# SKC_Display.net
KiCad netlist of a schematic drawn in Altium Designer
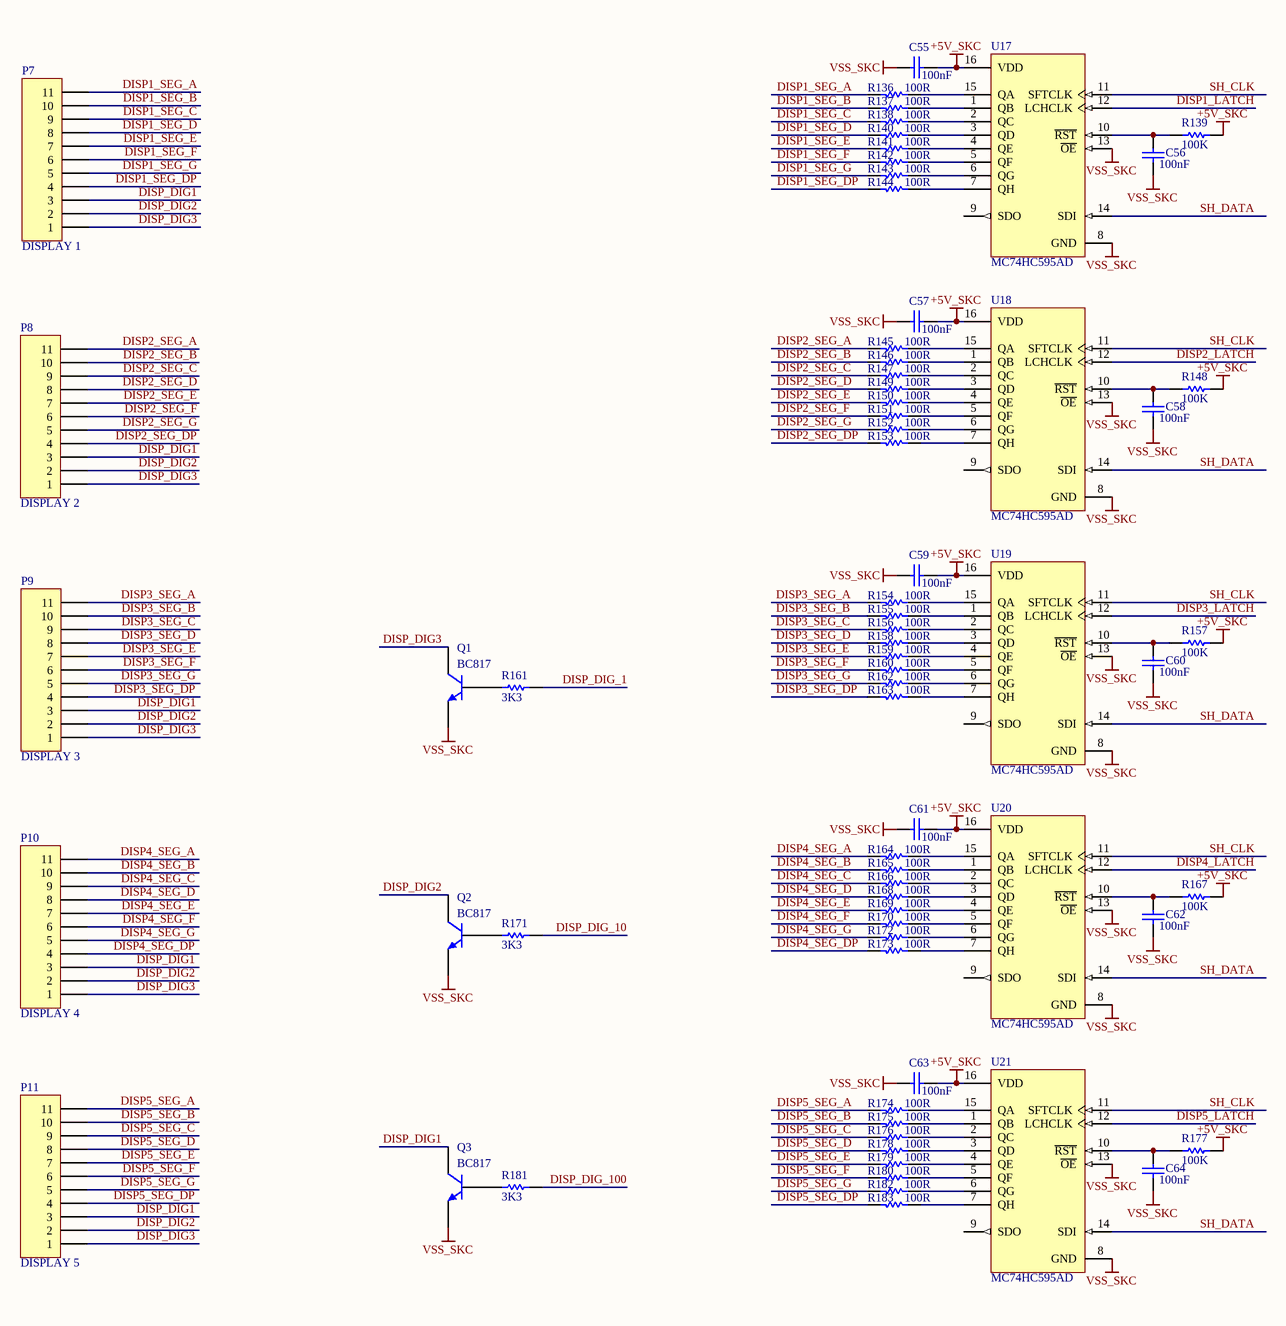
[diagram p0: SKC_Display.SchDoc]

(export (version "E")
  (design (tool "Eeschema 10.0.6"))
  (components
    (comp (ref "C55")
      (value "100nF")
      (footprint "1206")
      (description "Ceramic Chip Capacitor - Standard")
      (fields (field (name "PUBLISHER") "Altium Limited"))
      (libsource (lib "KEMET Chip Capacitor") (part "C1206"))
    )
    (comp (ref "C56")
      (value "100nF")
      (footprint "1206")
      (description "Ceramic Chip Capacitor - Standard")
      (fields (field (name "PUBLISHER") "Altium Limited"))
      (libsource (lib "KEMET Chip Capacitor") (part "C1206"))
    )
    (comp (ref "C57")
      (value "100nF")
      (footprint "1206")
      (description "Ceramic Chip Capacitor - Standard")
      (fields (field (name "PUBLISHER") "Altium Limited"))
      (libsource (lib "KEMET Chip Capacitor") (part "C1206"))
    )
    (comp (ref "C58")
      (value "100nF")
      (footprint "1206")
      (description "Ceramic Chip Capacitor - Standard")
      (fields (field (name "PUBLISHER") "Altium Limited"))
      (libsource (lib "KEMET Chip Capacitor") (part "C1206"))
    )
    (comp (ref "C59")
      (value "100nF")
      (footprint "1206")
      (description "Ceramic Chip Capacitor - Standard")
      (fields (field (name "PUBLISHER") "Altium Limited"))
      (libsource (lib "KEMET Chip Capacitor") (part "C1206"))
    )
    (comp (ref "C60")
      (value "100nF")
      (footprint "1206")
      (description "Ceramic Chip Capacitor - Standard")
      (fields (field (name "PUBLISHER") "Altium Limited"))
      (libsource (lib "KEMET Chip Capacitor") (part "C1206"))
    )
    (comp (ref "C61")
      (value "100nF")
      (footprint "1206")
      (description "Ceramic Chip Capacitor - Standard")
      (fields (field (name "PUBLISHER") "Altium Limited"))
      (libsource (lib "KEMET Chip Capacitor") (part "C1206"))
    )
    (comp (ref "C62")
      (value "100nF")
      (footprint "1206")
      (description "Ceramic Chip Capacitor - Standard")
      (fields (field (name "PUBLISHER") "Altium Limited"))
      (libsource (lib "KEMET Chip Capacitor") (part "C1206"))
    )
    (comp (ref "C63")
      (value "100nF")
      (footprint "1206")
      (description "Ceramic Chip Capacitor - Standard")
      (fields (field (name "PUBLISHER") "Altium Limited"))
      (libsource (lib "KEMET Chip Capacitor") (part "C1206"))
    )
    (comp (ref "C64")
      (value "100nF")
      (footprint "1206")
      (description "Ceramic Chip Capacitor - Standard")
      (fields (field (name "PUBLISHER") "Altium Limited"))
      (libsource (lib "KEMET Chip Capacitor") (part "C1206"))
    )
    (comp (ref "P7")
      (value "DISPLAY 1")
      (footprint "HDR1X11")
      (description "Header, 11-Pin")
      (fields (field (name "PUBLISHER") "Altium Limited"))
      (libsource (lib "Miscellaneous Connectors") (part "Header 11"))
    )
    (comp (ref "P8")
      (value "DISPLAY 2")
      (footprint "HDR1X11")
      (description "Header, 11-Pin")
      (fields (field (name "PUBLISHER") "Altium Limited"))
      (libsource (lib "Miscellaneous Connectors") (part "Header 11"))
    )
    (comp (ref "P9")
      (value "DISPLAY 3")
      (footprint "HDR1X11")
      (description "Header, 11-Pin")
      (fields (field (name "PUBLISHER") "Altium Limited"))
      (libsource (lib "Miscellaneous Connectors") (part "Header 11"))
    )
    (comp (ref "P10")
      (value "DISPLAY 4")
      (footprint "HDR1X11")
      (description "Header, 11-Pin")
      (fields (field (name "PUBLISHER") "Altium Limited"))
      (libsource (lib "Miscellaneous Connectors") (part "Header 11"))
    )
    (comp (ref "P11")
      (value "DISPLAY 5")
      (footprint "HDR1X11")
      (description "Header, 11-Pin")
      (fields (field (name "PUBLISHER") "Altium Limited"))
      (libsource (lib "Miscellaneous Connectors") (part "Header 11"))
    )
    (comp (ref "Q1")
      (value "BC817")
      (footprint "SOT23_N")
      (description "NPN General-purpose Transistor")
      (fields (field (name "PUBLISHER") "Altium Limited"))
      (libsource (lib "Philips Discrete BJT - Low Power") (part "BC817"))
    )
    (comp (ref "Q2")
      (value "BC817")
      (footprint "SOT23_N")
      (description "NPN General-purpose Transistor")
      (fields (field (name "PUBLISHER") "Altium Limited"))
      (libsource (lib "Philips Discrete BJT - Low Power") (part "BC817"))
    )
    (comp (ref "Q3")
      (value "BC817")
      (footprint "SOT23_N")
      (description "NPN General-purpose Transistor")
      (fields (field (name "PUBLISHER") "Altium Limited"))
      (libsource (lib "Philips Discrete BJT - Low Power") (part "BC817"))
    )
    (comp (ref "R136")
      (value "100R")
      (footprint "ERA-0603")
      (fields (field (name "PUBLISHER") "Altium Limited"))
      (libsource (lib "Panasonic Resistor") (part "ERA3Y"))
    )
    (comp (ref "R137")
      (value "100R")
      (footprint "ERA-0603")
      (fields (field (name "PUBLISHER") "Altium Limited"))
      (libsource (lib "Panasonic Resistor") (part "ERA3Y"))
    )
    (comp (ref "R138")
      (value "100R")
      (footprint "ERA-0603")
      (fields (field (name "PUBLISHER") "Altium Limited"))
      (libsource (lib "Panasonic Resistor") (part "ERA3Y"))
    )
    (comp (ref "R139")
      (value "100K")
      (footprint "ERA-0603")
      (fields (field (name "PUBLISHER") "Altium Limited"))
      (libsource (lib "Panasonic Resistor") (part "ERA3Y"))
    )
    (comp (ref "R140")
      (value "100R")
      (footprint "ERA-0603")
      (fields (field (name "PUBLISHER") "Altium Limited"))
      (libsource (lib "Panasonic Resistor") (part "ERA3Y"))
    )
    (comp (ref "R141")
      (value "100R")
      (footprint "ERA-0603")
      (fields (field (name "PUBLISHER") "Altium Limited"))
      (libsource (lib "Panasonic Resistor") (part "ERA3Y"))
    )
    (comp (ref "R142")
      (value "100R")
      (footprint "ERA-0603")
      (fields (field (name "PUBLISHER") "Altium Limited"))
      (libsource (lib "Panasonic Resistor") (part "ERA3Y"))
    )
    (comp (ref "R143")
      (value "100R")
      (footprint "ERA-0603")
      (fields (field (name "PUBLISHER") "Altium Limited"))
      (libsource (lib "Panasonic Resistor") (part "ERA3Y"))
    )
    (comp (ref "R144")
      (value "100R")
      (footprint "ERA-0603")
      (fields (field (name "PUBLISHER") "Altium Limited"))
      (libsource (lib "Panasonic Resistor") (part "ERA3Y"))
    )
    (comp (ref "R145")
      (value "100R")
      (footprint "ERA-0603")
      (fields (field (name "PUBLISHER") "Altium Limited"))
      (libsource (lib "Panasonic Resistor") (part "ERA3Y"))
    )
    (comp (ref "R146")
      (value "100R")
      (footprint "ERA-0603")
      (fields (field (name "PUBLISHER") "Altium Limited"))
      (libsource (lib "Panasonic Resistor") (part "ERA3Y"))
    )
    (comp (ref "R147")
      (value "100R")
      (footprint "ERA-0603")
      (fields (field (name "PUBLISHER") "Altium Limited"))
      (libsource (lib "Panasonic Resistor") (part "ERA3Y"))
    )
    (comp (ref "R148")
      (value "100K")
      (footprint "ERA-0603")
      (fields (field (name "PUBLISHER") "Altium Limited"))
      (libsource (lib "Panasonic Resistor") (part "ERA3Y"))
    )
    (comp (ref "R149")
      (value "100R")
      (footprint "ERA-0603")
      (fields (field (name "PUBLISHER") "Altium Limited"))
      (libsource (lib "Panasonic Resistor") (part "ERA3Y"))
    )
    (comp (ref "R150")
      (value "100R")
      (footprint "ERA-0603")
      (fields (field (name "PUBLISHER") "Altium Limited"))
      (libsource (lib "Panasonic Resistor") (part "ERA3Y"))
    )
    (comp (ref "R151")
      (value "100R")
      (footprint "ERA-0603")
      (fields (field (name "PUBLISHER") "Altium Limited"))
      (libsource (lib "Panasonic Resistor") (part "ERA3Y"))
    )
    (comp (ref "R152")
      (value "100R")
      (footprint "ERA-0603")
      (fields (field (name "PUBLISHER") "Altium Limited"))
      (libsource (lib "Panasonic Resistor") (part "ERA3Y"))
    )
    (comp (ref "R153")
      (value "100R")
      (footprint "ERA-0603")
      (fields (field (name "PUBLISHER") "Altium Limited"))
      (libsource (lib "Panasonic Resistor") (part "ERA3Y"))
    )
    (comp (ref "R154")
      (value "100R")
      (footprint "ERA-0603")
      (fields (field (name "PUBLISHER") "Altium Limited"))
      (libsource (lib "Panasonic Resistor") (part "ERA3Y"))
    )
    (comp (ref "R155")
      (value "100R")
      (footprint "ERA-0603")
      (fields (field (name "PUBLISHER") "Altium Limited"))
      (libsource (lib "Panasonic Resistor") (part "ERA3Y"))
    )
    (comp (ref "R156")
      (value "100R")
      (footprint "ERA-0603")
      (fields (field (name "PUBLISHER") "Altium Limited"))
      (libsource (lib "Panasonic Resistor") (part "ERA3Y"))
    )
    (comp (ref "R157")
      (value "100K")
      (footprint "ERA-0603")
      (fields (field (name "PUBLISHER") "Altium Limited"))
      (libsource (lib "Panasonic Resistor") (part "ERA3Y"))
    )
    (comp (ref "R158")
      (value "100R")
      (footprint "ERA-0603")
      (fields (field (name "PUBLISHER") "Altium Limited"))
      (libsource (lib "Panasonic Resistor") (part "ERA3Y"))
    )
    (comp (ref "R159")
      (value "100R")
      (footprint "ERA-0603")
      (fields (field (name "PUBLISHER") "Altium Limited"))
      (libsource (lib "Panasonic Resistor") (part "ERA3Y"))
    )
    (comp (ref "R160")
      (value "100R")
      (footprint "ERA-0603")
      (fields (field (name "PUBLISHER") "Altium Limited"))
      (libsource (lib "Panasonic Resistor") (part "ERA3Y"))
    )
    (comp (ref "R161")
      (value "3K3")
      (footprint "ERA-0603")
      (fields (field (name "PUBLISHER") "Altium Limited"))
      (libsource (lib "Panasonic Resistor") (part "ERA3Y"))
    )
    (comp (ref "R162")
      (value "100R")
      (footprint "ERA-0603")
      (fields (field (name "PUBLISHER") "Altium Limited"))
      (libsource (lib "Panasonic Resistor") (part "ERA3Y"))
    )
    (comp (ref "R163")
      (value "100R")
      (footprint "ERA-0603")
      (fields (field (name "PUBLISHER") "Altium Limited"))
      (libsource (lib "Panasonic Resistor") (part "ERA3Y"))
    )
    (comp (ref "R164")
      (value "100R")
      (footprint "ERA-0603")
      (fields (field (name "PUBLISHER") "Altium Limited"))
      (libsource (lib "Panasonic Resistor") (part "ERA3Y"))
    )
    (comp (ref "R165")
      (value "100R")
      (footprint "ERA-0603")
      (fields (field (name "PUBLISHER") "Altium Limited"))
      (libsource (lib "Panasonic Resistor") (part "ERA3Y"))
    )
    (comp (ref "R166")
      (value "100R")
      (footprint "ERA-0603")
      (fields (field (name "PUBLISHER") "Altium Limited"))
      (libsource (lib "Panasonic Resistor") (part "ERA3Y"))
    )
    (comp (ref "R167")
      (value "100K")
      (footprint "ERA-0603")
      (fields (field (name "PUBLISHER") "Altium Limited"))
      (libsource (lib "Panasonic Resistor") (part "ERA3Y"))
    )
    (comp (ref "R168")
      (value "100R")
      (footprint "ERA-0603")
      (fields (field (name "PUBLISHER") "Altium Limited"))
      (libsource (lib "Panasonic Resistor") (part "ERA3Y"))
    )
    (comp (ref "R169")
      (value "100R")
      (footprint "ERA-0603")
      (fields (field (name "PUBLISHER") "Altium Limited"))
      (libsource (lib "Panasonic Resistor") (part "ERA3Y"))
    )
    (comp (ref "R170")
      (value "100R")
      (footprint "ERA-0603")
      (fields (field (name "PUBLISHER") "Altium Limited"))
      (libsource (lib "Panasonic Resistor") (part "ERA3Y"))
    )
    (comp (ref "R171")
      (value "3K3")
      (footprint "ERA-0603")
      (fields (field (name "PUBLISHER") "Altium Limited"))
      (libsource (lib "Panasonic Resistor") (part "ERA3Y"))
    )
    (comp (ref "R172")
      (value "100R")
      (footprint "ERA-0603")
      (fields (field (name "PUBLISHER") "Altium Limited"))
      (libsource (lib "Panasonic Resistor") (part "ERA3Y"))
    )
    (comp (ref "R173")
      (value "100R")
      (footprint "ERA-0603")
      (fields (field (name "PUBLISHER") "Altium Limited"))
      (libsource (lib "Panasonic Resistor") (part "ERA3Y"))
    )
    (comp (ref "R174")
      (value "100R")
      (footprint "ERA-0603")
      (fields (field (name "PUBLISHER") "Altium Limited"))
      (libsource (lib "Panasonic Resistor") (part "ERA3Y"))
    )
    (comp (ref "R175")
      (value "100R")
      (footprint "ERA-0603")
      (fields (field (name "PUBLISHER") "Altium Limited"))
      (libsource (lib "Panasonic Resistor") (part "ERA3Y"))
    )
    (comp (ref "R176")
      (value "100R")
      (footprint "ERA-0603")
      (fields (field (name "PUBLISHER") "Altium Limited"))
      (libsource (lib "Panasonic Resistor") (part "ERA3Y"))
    )
    (comp (ref "R177")
      (value "100K")
      (footprint "ERA-0603")
      (fields (field (name "PUBLISHER") "Altium Limited"))
      (libsource (lib "Panasonic Resistor") (part "ERA3Y"))
    )
    (comp (ref "R178")
      (value "100R")
      (footprint "ERA-0603")
      (fields (field (name "PUBLISHER") "Altium Limited"))
      (libsource (lib "Panasonic Resistor") (part "ERA3Y"))
    )
    (comp (ref "R179")
      (value "100R")
      (footprint "ERA-0603")
      (fields (field (name "PUBLISHER") "Altium Limited"))
      (libsource (lib "Panasonic Resistor") (part "ERA3Y"))
    )
    (comp (ref "R180")
      (value "100R")
      (footprint "ERA-0603")
      (fields (field (name "PUBLISHER") "Altium Limited"))
      (libsource (lib "Panasonic Resistor") (part "ERA3Y"))
    )
    (comp (ref "R181")
      (value "3K3")
      (footprint "ERA-0603")
      (fields (field (name "PUBLISHER") "Altium Limited"))
      (libsource (lib "Panasonic Resistor") (part "ERA3Y"))
    )
    (comp (ref "R182")
      (value "100R")
      (footprint "ERA-0603")
      (fields (field (name "PUBLISHER") "Altium Limited"))
      (libsource (lib "Panasonic Resistor") (part "ERA3Y"))
    )
    (comp (ref "R183")
      (value "100R")
      (footprint "ERA-0603")
      (fields (field (name "PUBLISHER") "Altium Limited"))
      (libsource (lib "Panasonic Resistor") (part "ERA3Y"))
    )
    (comp (ref "U17")
      (value "MC74HC595AD")
      (footprint "751B-05_N")
      (description "8-Bit Serial-Input/Serial or Prallel-Output Shift Register with Latched 3-State Outputs")
      (fields (field (name "PUBLISHER") "Altium Limited"))
      (libsource (lib "ON Semi Logic Register") (part "MC74HC595AD"))
    )
    (comp (ref "U18")
      (value "MC74HC595AD")
      (footprint "751B-05_N")
      (description "8-Bit Serial-Input/Serial or Prallel-Output Shift Register with Latched 3-State Outputs")
      (fields (field (name "PUBLISHER") "Altium Limited"))
      (libsource (lib "ON Semi Logic Register") (part "MC74HC595AD"))
    )
    (comp (ref "U19")
      (value "MC74HC595AD")
      (footprint "751B-05_N")
      (description "8-Bit Serial-Input/Serial or Prallel-Output Shift Register with Latched 3-State Outputs")
      (fields (field (name "PUBLISHER") "Altium Limited"))
      (libsource (lib "ON Semi Logic Register") (part "MC74HC595AD"))
    )
    (comp (ref "U20")
      (value "MC74HC595AD")
      (footprint "751B-05_N")
      (description "8-Bit Serial-Input/Serial or Prallel-Output Shift Register with Latched 3-State Outputs")
      (fields (field (name "PUBLISHER") "Altium Limited"))
      (libsource (lib "ON Semi Logic Register") (part "MC74HC595AD"))
    )
    (comp (ref "U21")
      (value "MC74HC595AD")
      (footprint "751B-05_N")
      (description "8-Bit Serial-Input/Serial or Prallel-Output Shift Register with Latched 3-State Outputs")
      (fields (field (name "PUBLISHER") "Altium Limited"))
      (libsource (lib "ON Semi Logic Register") (part "MC74HC595AD"))
    )
  )
  (nets
    (net (code "1") (name "+5V_SKC") (class "Default")
      (node (ref "C55") (pin "1") (pinfunction "1_1") (pintype "passive"))
      (node (ref "C57") (pin "1") (pinfunction "1_1") (pintype "passive"))
      (node (ref "C59") (pin "1") (pinfunction "1_1") (pintype "passive"))
      (node (ref "C61") (pin "1") (pinfunction "1_1") (pintype "passive"))
      (node (ref "C63") (pin "1") (pinfunction "1_1") (pintype "passive"))
      (node (ref "R139") (pin "2") (pinfunction "2_2") (pintype "passive"))
      (node (ref "R148") (pin "2") (pinfunction "2_2") (pintype "passive"))
      (node (ref "R157") (pin "2") (pinfunction "2_2") (pintype "passive"))
      (node (ref "R167") (pin "2") (pinfunction "2_2") (pintype "passive"))
      (node (ref "R177") (pin "2") (pinfunction "2_2") (pintype "passive"))
      (node (ref "U17") (pin "16") (pinfunction "VDD_16") (pintype "power_in"))
      (node (ref "U18") (pin "16") (pinfunction "VDD_16") (pintype "power_in"))
      (node (ref "U19") (pin "16") (pinfunction "VDD_16") (pintype "power_in"))
      (node (ref "U20") (pin "16") (pinfunction "VDD_16") (pintype "power_in"))
      (node (ref "U21") (pin "16") (pinfunction "VDD_16") (pintype "power_in"))
    )
    (net (code "2") (name "/DISP1_LATCH") (class "Default")
      (node (ref "U17") (pin "12") (pinfunction "LCHCLK_12") (pintype "input"))
    )
    (net (code "3") (name "/DISP1_SEG_A") (class "Default")
      (node (ref "P7") (pin "11") (pinfunction "11_11") (pintype "passive"))
      (node (ref "R136") (pin "2") (pinfunction "2_2") (pintype "passive"))
    )
    (net (code "4") (name "/DISP1_SEG_B") (class "Default")
      (node (ref "P7") (pin "10") (pinfunction "10_10") (pintype "passive"))
      (node (ref "R137") (pin "2") (pinfunction "2_2") (pintype "passive"))
    )
    (net (code "5") (name "/DISP1_SEG_C") (class "Default")
      (node (ref "P7") (pin "9") (pinfunction "9_9") (pintype "passive"))
      (node (ref "R138") (pin "2") (pinfunction "2_2") (pintype "passive"))
    )
    (net (code "6") (name "/DISP1_SEG_D") (class "Default")
      (node (ref "P7") (pin "8") (pinfunction "8_8") (pintype "passive"))
      (node (ref "R140") (pin "2") (pinfunction "2_2") (pintype "passive"))
    )
    (net (code "7") (name "/DISP1_SEG_DP") (class "Default")
      (node (ref "P7") (pin "4") (pinfunction "4_4") (pintype "passive"))
      (node (ref "R144") (pin "2") (pinfunction "2_2") (pintype "passive"))
    )
    (net (code "8") (name "/DISP1_SEG_E") (class "Default")
      (node (ref "P7") (pin "7") (pinfunction "7_7") (pintype "passive"))
      (node (ref "R141") (pin "2") (pinfunction "2_2") (pintype "passive"))
    )
    (net (code "9") (name "/DISP1_SEG_F") (class "Default")
      (node (ref "P7") (pin "6") (pinfunction "6_6") (pintype "passive"))
      (node (ref "R142") (pin "2") (pinfunction "2_2") (pintype "passive"))
    )
    (net (code "10") (name "/DISP1_SEG_G") (class "Default")
      (node (ref "P7") (pin "5") (pinfunction "5_5") (pintype "passive"))
      (node (ref "R143") (pin "2") (pinfunction "2_2") (pintype "passive"))
    )
    (net (code "11") (name "/DISP2_LATCH") (class "Default")
      (node (ref "U18") (pin "12") (pinfunction "LCHCLK_12") (pintype "input"))
    )
    (net (code "12") (name "/DISP2_SEG_A") (class "Default")
      (node (ref "P8") (pin "11") (pinfunction "11_11") (pintype "passive"))
      (node (ref "R145") (pin "2") (pinfunction "2_2") (pintype "passive"))
    )
    (net (code "13") (name "/DISP2_SEG_B") (class "Default")
      (node (ref "P8") (pin "10") (pinfunction "10_10") (pintype "passive"))
      (node (ref "R146") (pin "2") (pinfunction "2_2") (pintype "passive"))
    )
    (net (code "14") (name "/DISP2_SEG_C") (class "Default")
      (node (ref "P8") (pin "9") (pinfunction "9_9") (pintype "passive"))
      (node (ref "R147") (pin "2") (pinfunction "2_2") (pintype "passive"))
    )
    (net (code "15") (name "/DISP2_SEG_D") (class "Default")
      (node (ref "P8") (pin "8") (pinfunction "8_8") (pintype "passive"))
      (node (ref "R149") (pin "2") (pinfunction "2_2") (pintype "passive"))
    )
    (net (code "16") (name "/DISP2_SEG_DP") (class "Default")
      (node (ref "P8") (pin "4") (pinfunction "4_4") (pintype "passive"))
      (node (ref "R153") (pin "2") (pinfunction "2_2") (pintype "passive"))
    )
    (net (code "17") (name "/DISP2_SEG_E") (class "Default")
      (node (ref "P8") (pin "7") (pinfunction "7_7") (pintype "passive"))
      (node (ref "R150") (pin "2") (pinfunction "2_2") (pintype "passive"))
    )
    (net (code "18") (name "/DISP2_SEG_F") (class "Default")
      (node (ref "P8") (pin "6") (pinfunction "6_6") (pintype "passive"))
      (node (ref "R151") (pin "2") (pinfunction "2_2") (pintype "passive"))
    )
    (net (code "19") (name "/DISP2_SEG_G") (class "Default")
      (node (ref "P8") (pin "5") (pinfunction "5_5") (pintype "passive"))
      (node (ref "R152") (pin "2") (pinfunction "2_2") (pintype "passive"))
    )
    (net (code "20") (name "/DISP3_LATCH") (class "Default")
      (node (ref "U19") (pin "12") (pinfunction "LCHCLK_12") (pintype "input"))
    )
    (net (code "21") (name "/DISP3_SEG_A") (class "Default")
      (node (ref "P9") (pin "11") (pinfunction "11_11") (pintype "passive"))
      (node (ref "R154") (pin "2") (pinfunction "2_2") (pintype "passive"))
    )
    (net (code "22") (name "/DISP3_SEG_B") (class "Default")
      (node (ref "P9") (pin "10") (pinfunction "10_10") (pintype "passive"))
      (node (ref "R155") (pin "2") (pinfunction "2_2") (pintype "passive"))
    )
    (net (code "23") (name "/DISP3_SEG_C") (class "Default")
      (node (ref "P9") (pin "9") (pinfunction "9_9") (pintype "passive"))
      (node (ref "R156") (pin "2") (pinfunction "2_2") (pintype "passive"))
    )
    (net (code "24") (name "/DISP3_SEG_D") (class "Default")
      (node (ref "P9") (pin "8") (pinfunction "8_8") (pintype "passive"))
      (node (ref "R158") (pin "2") (pinfunction "2_2") (pintype "passive"))
    )
    (net (code "25") (name "/DISP3_SEG_DP") (class "Default")
      (node (ref "P9") (pin "4") (pinfunction "4_4") (pintype "passive"))
      (node (ref "R163") (pin "2") (pinfunction "2_2") (pintype "passive"))
    )
    (net (code "26") (name "/DISP3_SEG_E") (class "Default")
      (node (ref "P9") (pin "7") (pinfunction "7_7") (pintype "passive"))
      (node (ref "R159") (pin "2") (pinfunction "2_2") (pintype "passive"))
    )
    (net (code "27") (name "/DISP3_SEG_F") (class "Default")
      (node (ref "P9") (pin "6") (pinfunction "6_6") (pintype "passive"))
      (node (ref "R160") (pin "2") (pinfunction "2_2") (pintype "passive"))
    )
    (net (code "28") (name "/DISP3_SEG_G") (class "Default")
      (node (ref "P9") (pin "5") (pinfunction "5_5") (pintype "passive"))
      (node (ref "R162") (pin "2") (pinfunction "2_2") (pintype "passive"))
    )
    (net (code "29") (name "/DISP4_LATCH") (class "Default")
      (node (ref "U20") (pin "12") (pinfunction "LCHCLK_12") (pintype "input"))
    )
    (net (code "30") (name "/DISP4_SEG_A") (class "Default")
      (node (ref "P10") (pin "11") (pinfunction "11_11") (pintype "passive"))
      (node (ref "R164") (pin "2") (pinfunction "2_2") (pintype "passive"))
    )
    (net (code "31") (name "/DISP4_SEG_B") (class "Default")
      (node (ref "P10") (pin "10") (pinfunction "10_10") (pintype "passive"))
      (node (ref "R165") (pin "2") (pinfunction "2_2") (pintype "passive"))
    )
    (net (code "32") (name "/DISP4_SEG_C") (class "Default")
      (node (ref "P10") (pin "9") (pinfunction "9_9") (pintype "passive"))
      (node (ref "R166") (pin "2") (pinfunction "2_2") (pintype "passive"))
    )
    (net (code "33") (name "/DISP4_SEG_D") (class "Default")
      (node (ref "P10") (pin "8") (pinfunction "8_8") (pintype "passive"))
      (node (ref "R168") (pin "2") (pinfunction "2_2") (pintype "passive"))
    )
    (net (code "34") (name "/DISP4_SEG_DP") (class "Default")
      (node (ref "P10") (pin "4") (pinfunction "4_4") (pintype "passive"))
      (node (ref "R173") (pin "2") (pinfunction "2_2") (pintype "passive"))
    )
    (net (code "35") (name "/DISP4_SEG_E") (class "Default")
      (node (ref "P10") (pin "7") (pinfunction "7_7") (pintype "passive"))
      (node (ref "R169") (pin "2") (pinfunction "2_2") (pintype "passive"))
    )
    (net (code "36") (name "/DISP4_SEG_F") (class "Default")
      (node (ref "P10") (pin "6") (pinfunction "6_6") (pintype "passive"))
      (node (ref "R170") (pin "2") (pinfunction "2_2") (pintype "passive"))
    )
    (net (code "37") (name "/DISP4_SEG_G") (class "Default")
      (node (ref "P10") (pin "5") (pinfunction "5_5") (pintype "passive"))
      (node (ref "R172") (pin "2") (pinfunction "2_2") (pintype "passive"))
    )
    (net (code "38") (name "/DISP5_LATCH") (class "Default")
      (node (ref "U21") (pin "12") (pinfunction "LCHCLK_12") (pintype "input"))
    )
    (net (code "39") (name "/DISP5_SEG_A") (class "Default")
      (node (ref "P11") (pin "11") (pinfunction "11_11") (pintype "passive"))
      (node (ref "R174") (pin "2") (pinfunction "2_2") (pintype "passive"))
    )
    (net (code "40") (name "/DISP5_SEG_B") (class "Default")
      (node (ref "P11") (pin "10") (pinfunction "10_10") (pintype "passive"))
      (node (ref "R175") (pin "2") (pinfunction "2_2") (pintype "passive"))
    )
    (net (code "41") (name "/DISP5_SEG_C") (class "Default")
      (node (ref "P11") (pin "9") (pinfunction "9_9") (pintype "passive"))
      (node (ref "R176") (pin "2") (pinfunction "2_2") (pintype "passive"))
    )
    (net (code "42") (name "/DISP5_SEG_D") (class "Default")
      (node (ref "P11") (pin "8") (pinfunction "8_8") (pintype "passive"))
      (node (ref "R178") (pin "2") (pinfunction "2_2") (pintype "passive"))
    )
    (net (code "43") (name "/DISP5_SEG_DP") (class "Default")
      (node (ref "P11") (pin "4") (pinfunction "4_4") (pintype "passive"))
      (node (ref "R183") (pin "2") (pinfunction "2_2") (pintype "passive"))
    )
    (net (code "44") (name "/DISP5_SEG_E") (class "Default")
      (node (ref "P11") (pin "7") (pinfunction "7_7") (pintype "passive"))
      (node (ref "R179") (pin "2") (pinfunction "2_2") (pintype "passive"))
    )
    (net (code "45") (name "/DISP5_SEG_F") (class "Default")
      (node (ref "P11") (pin "6") (pinfunction "6_6") (pintype "passive"))
      (node (ref "R180") (pin "2") (pinfunction "2_2") (pintype "passive"))
    )
    (net (code "46") (name "/DISP5_SEG_G") (class "Default")
      (node (ref "P11") (pin "5") (pinfunction "5_5") (pintype "passive"))
      (node (ref "R182") (pin "2") (pinfunction "2_2") (pintype "passive"))
    )
    (net (code "47") (name "/DISP_DIG1") (class "Default")
      (node (ref "P10") (pin "3") (pinfunction "3_3") (pintype "passive"))
      (node (ref "P11") (pin "3") (pinfunction "3_3") (pintype "passive"))
      (node (ref "P7") (pin "3") (pinfunction "3_3") (pintype "passive"))
      (node (ref "P8") (pin "3") (pinfunction "3_3") (pintype "passive"))
      (node (ref "P9") (pin "3") (pinfunction "3_3") (pintype "passive"))
      (node (ref "Q3") (pin "3") (pinfunction "C_3") (pintype "passive"))
    )
    (net (code "48") (name "/DISP_DIG2") (class "Default")
      (node (ref "P10") (pin "2") (pinfunction "2_2") (pintype "passive"))
      (node (ref "P11") (pin "2") (pinfunction "2_2") (pintype "passive"))
      (node (ref "P7") (pin "2") (pinfunction "2_2") (pintype "passive"))
      (node (ref "P8") (pin "2") (pinfunction "2_2") (pintype "passive"))
      (node (ref "P9") (pin "2") (pinfunction "2_2") (pintype "passive"))
      (node (ref "Q2") (pin "3") (pinfunction "C_3") (pintype "passive"))
    )
    (net (code "49") (name "/DISP_DIG3") (class "Default")
      (node (ref "P10") (pin "1") (pinfunction "1_1") (pintype "passive"))
      (node (ref "P11") (pin "1") (pinfunction "1_1") (pintype "passive"))
      (node (ref "P7") (pin "1") (pinfunction "1_1") (pintype "passive"))
      (node (ref "P8") (pin "1") (pinfunction "1_1") (pintype "passive"))
      (node (ref "P9") (pin "1") (pinfunction "1_1") (pintype "passive"))
      (node (ref "Q1") (pin "3") (pinfunction "C_3") (pintype "passive"))
    )
    (net (code "50") (name "/DISP_DIG_1") (class "Default")
      (node (ref "R161") (pin "2") (pinfunction "2_2") (pintype "passive"))
    )
    (net (code "51") (name "/DISP_DIG_10") (class "Default")
      (node (ref "R171") (pin "2") (pinfunction "2_2") (pintype "passive"))
    )
    (net (code "52") (name "/DISP_DIG_100") (class "Default")
      (node (ref "R181") (pin "2") (pinfunction "2_2") (pintype "passive"))
    )
    (net (code "53") (name "/SH_CLK") (class "Default")
      (node (ref "U17") (pin "11") (pinfunction "SFTCLK_11") (pintype "input"))
      (node (ref "U18") (pin "11") (pinfunction "SFTCLK_11") (pintype "input"))
      (node (ref "U19") (pin "11") (pinfunction "SFTCLK_11") (pintype "input"))
      (node (ref "U20") (pin "11") (pinfunction "SFTCLK_11") (pintype "input"))
      (node (ref "U21") (pin "11") (pinfunction "SFTCLK_11") (pintype "input"))
    )
    (net (code "54") (name "/SH_DATA") (class "Default")
      (node (ref "U17") (pin "14") (pinfunction "SDI_14") (pintype "input"))
      (node (ref "U18") (pin "14") (pinfunction "SDI_14") (pintype "input"))
      (node (ref "U19") (pin "14") (pinfunction "SDI_14") (pintype "input"))
      (node (ref "U20") (pin "14") (pinfunction "SDI_14") (pintype "input"))
      (node (ref "U21") (pin "14") (pinfunction "SDI_14") (pintype "input"))
    )
    (net (code "55") (name "Net-(Q1-B)") (class "Default")
      (node (ref "Q1") (pin "1") (pinfunction "B_1") (pintype "passive"))
      (node (ref "R161") (pin "1") (pinfunction "1_1") (pintype "passive"))
    )
    (net (code "56") (name "Net-(Q2-B)") (class "Default")
      (node (ref "Q2") (pin "1") (pinfunction "B_1") (pintype "passive"))
      (node (ref "R171") (pin "1") (pinfunction "1_1") (pintype "passive"))
    )
    (net (code "57") (name "Net-(Q3-B)") (class "Default")
      (node (ref "Q3") (pin "1") (pinfunction "B_1") (pintype "passive"))
      (node (ref "R181") (pin "1") (pinfunction "1_1") (pintype "passive"))
    )
    (net (code "58") (name "Net-(U17-QA)") (class "Default")
      (node (ref "R136") (pin "1") (pinfunction "1_1") (pintype "passive"))
      (node (ref "U17") (pin "15") (pinfunction "QA_15") (pintype "tri_state"))
    )
    (net (code "59") (name "Net-(U17-QB)") (class "Default")
      (node (ref "R137") (pin "1") (pinfunction "1_1") (pintype "passive"))
      (node (ref "U17") (pin "1") (pinfunction "QB_1") (pintype "tri_state"))
    )
    (net (code "60") (name "Net-(U17-QC)") (class "Default")
      (node (ref "R138") (pin "1") (pinfunction "1_1") (pintype "passive"))
      (node (ref "U17") (pin "2") (pinfunction "QC_2") (pintype "tri_state"))
    )
    (net (code "61") (name "Net-(U17-QD)") (class "Default")
      (node (ref "R140") (pin "1") (pinfunction "1_1") (pintype "passive"))
      (node (ref "U17") (pin "3") (pinfunction "QD_3") (pintype "tri_state"))
    )
    (net (code "62") (name "Net-(U17-QE)") (class "Default")
      (node (ref "R141") (pin "1") (pinfunction "1_1") (pintype "passive"))
      (node (ref "U17") (pin "4") (pinfunction "QE_4") (pintype "tri_state"))
    )
    (net (code "63") (name "Net-(U17-QF)") (class "Default")
      (node (ref "R142") (pin "1") (pinfunction "1_1") (pintype "passive"))
      (node (ref "U17") (pin "5") (pinfunction "QF_5") (pintype "tri_state"))
    )
    (net (code "64") (name "Net-(U17-QG)") (class "Default")
      (node (ref "R143") (pin "1") (pinfunction "1_1") (pintype "passive"))
      (node (ref "U17") (pin "6") (pinfunction "QG_6") (pintype "tri_state"))
    )
    (net (code "65") (name "Net-(U17-QH)") (class "Default")
      (node (ref "R144") (pin "1") (pinfunction "1_1") (pintype "passive"))
      (node (ref "U17") (pin "7") (pinfunction "QH_7") (pintype "tri_state"))
    )
    (net (code "66") (name "Net-(U17-~{RST})") (class "Default")
      (node (ref "C56") (pin "2") (pinfunction "2_2") (pintype "passive"))
      (node (ref "R139") (pin "1") (pinfunction "1_1") (pintype "passive"))
      (node (ref "U17") (pin "10") (pinfunction "~{RST}_10") (pintype "input"))
    )
    (net (code "67") (name "Net-(U18-QA)") (class "Default")
      (node (ref "R145") (pin "1") (pinfunction "1_1") (pintype "passive"))
      (node (ref "U18") (pin "15") (pinfunction "QA_15") (pintype "tri_state"))
    )
    (net (code "68") (name "Net-(U18-QB)") (class "Default")
      (node (ref "R146") (pin "1") (pinfunction "1_1") (pintype "passive"))
      (node (ref "U18") (pin "1") (pinfunction "QB_1") (pintype "tri_state"))
    )
    (net (code "69") (name "Net-(U18-QC)") (class "Default")
      (node (ref "R147") (pin "1") (pinfunction "1_1") (pintype "passive"))
      (node (ref "U18") (pin "2") (pinfunction "QC_2") (pintype "tri_state"))
    )
    (net (code "70") (name "Net-(U18-QD)") (class "Default")
      (node (ref "R149") (pin "1") (pinfunction "1_1") (pintype "passive"))
      (node (ref "U18") (pin "3") (pinfunction "QD_3") (pintype "tri_state"))
    )
    (net (code "71") (name "Net-(U18-QE)") (class "Default")
      (node (ref "R150") (pin "1") (pinfunction "1_1") (pintype "passive"))
      (node (ref "U18") (pin "4") (pinfunction "QE_4") (pintype "tri_state"))
    )
    (net (code "72") (name "Net-(U18-QF)") (class "Default")
      (node (ref "R151") (pin "1") (pinfunction "1_1") (pintype "passive"))
      (node (ref "U18") (pin "5") (pinfunction "QF_5") (pintype "tri_state"))
    )
    (net (code "73") (name "Net-(U18-QG)") (class "Default")
      (node (ref "R152") (pin "1") (pinfunction "1_1") (pintype "passive"))
      (node (ref "U18") (pin "6") (pinfunction "QG_6") (pintype "tri_state"))
    )
    (net (code "74") (name "Net-(U18-QH)") (class "Default")
      (node (ref "R153") (pin "1") (pinfunction "1_1") (pintype "passive"))
      (node (ref "U18") (pin "7") (pinfunction "QH_7") (pintype "tri_state"))
    )
    (net (code "75") (name "Net-(U18-~{RST})") (class "Default")
      (node (ref "C58") (pin "2") (pinfunction "2_2") (pintype "passive"))
      (node (ref "R148") (pin "1") (pinfunction "1_1") (pintype "passive"))
      (node (ref "U18") (pin "10") (pinfunction "~{RST}_10") (pintype "input"))
    )
    (net (code "76") (name "Net-(U19-QA)") (class "Default")
      (node (ref "R154") (pin "1") (pinfunction "1_1") (pintype "passive"))
      (node (ref "U19") (pin "15") (pinfunction "QA_15") (pintype "tri_state"))
    )
    (net (code "77") (name "Net-(U19-QB)") (class "Default")
      (node (ref "R155") (pin "1") (pinfunction "1_1") (pintype "passive"))
      (node (ref "U19") (pin "1") (pinfunction "QB_1") (pintype "tri_state"))
    )
    (net (code "78") (name "Net-(U19-QC)") (class "Default")
      (node (ref "R156") (pin "1") (pinfunction "1_1") (pintype "passive"))
      (node (ref "U19") (pin "2") (pinfunction "QC_2") (pintype "tri_state"))
    )
    (net (code "79") (name "Net-(U19-QD)") (class "Default")
      (node (ref "R158") (pin "1") (pinfunction "1_1") (pintype "passive"))
      (node (ref "U19") (pin "3") (pinfunction "QD_3") (pintype "tri_state"))
    )
    (net (code "80") (name "Net-(U19-QE)") (class "Default")
      (node (ref "R159") (pin "1") (pinfunction "1_1") (pintype "passive"))
      (node (ref "U19") (pin "4") (pinfunction "QE_4") (pintype "tri_state"))
    )
    (net (code "81") (name "Net-(U19-QF)") (class "Default")
      (node (ref "R160") (pin "1") (pinfunction "1_1") (pintype "passive"))
      (node (ref "U19") (pin "5") (pinfunction "QF_5") (pintype "tri_state"))
    )
    (net (code "82") (name "Net-(U19-QG)") (class "Default")
      (node (ref "R162") (pin "1") (pinfunction "1_1") (pintype "passive"))
      (node (ref "U19") (pin "6") (pinfunction "QG_6") (pintype "tri_state"))
    )
    (net (code "83") (name "Net-(U19-QH)") (class "Default")
      (node (ref "R163") (pin "1") (pinfunction "1_1") (pintype "passive"))
      (node (ref "U19") (pin "7") (pinfunction "QH_7") (pintype "tri_state"))
    )
    (net (code "84") (name "Net-(U19-~{RST})") (class "Default")
      (node (ref "C60") (pin "2") (pinfunction "2_2") (pintype "passive"))
      (node (ref "R157") (pin "1") (pinfunction "1_1") (pintype "passive"))
      (node (ref "U19") (pin "10") (pinfunction "~{RST}_10") (pintype "input"))
    )
    (net (code "85") (name "Net-(U20-QA)") (class "Default")
      (node (ref "R164") (pin "1") (pinfunction "1_1") (pintype "passive"))
      (node (ref "U20") (pin "15") (pinfunction "QA_15") (pintype "tri_state"))
    )
    (net (code "86") (name "Net-(U20-QB)") (class "Default")
      (node (ref "R165") (pin "1") (pinfunction "1_1") (pintype "passive"))
      (node (ref "U20") (pin "1") (pinfunction "QB_1") (pintype "tri_state"))
    )
    (net (code "87") (name "Net-(U20-QC)") (class "Default")
      (node (ref "R166") (pin "1") (pinfunction "1_1") (pintype "passive"))
      (node (ref "U20") (pin "2") (pinfunction "QC_2") (pintype "tri_state"))
    )
    (net (code "88") (name "Net-(U20-QD)") (class "Default")
      (node (ref "R168") (pin "1") (pinfunction "1_1") (pintype "passive"))
      (node (ref "U20") (pin "3") (pinfunction "QD_3") (pintype "tri_state"))
    )
    (net (code "89") (name "Net-(U20-QE)") (class "Default")
      (node (ref "R169") (pin "1") (pinfunction "1_1") (pintype "passive"))
      (node (ref "U20") (pin "4") (pinfunction "QE_4") (pintype "tri_state"))
    )
    (net (code "90") (name "Net-(U20-QF)") (class "Default")
      (node (ref "R170") (pin "1") (pinfunction "1_1") (pintype "passive"))
      (node (ref "U20") (pin "5") (pinfunction "QF_5") (pintype "tri_state"))
    )
    (net (code "91") (name "Net-(U20-QG)") (class "Default")
      (node (ref "R172") (pin "1") (pinfunction "1_1") (pintype "passive"))
      (node (ref "U20") (pin "6") (pinfunction "QG_6") (pintype "tri_state"))
    )
    (net (code "92") (name "Net-(U20-QH)") (class "Default")
      (node (ref "R173") (pin "1") (pinfunction "1_1") (pintype "passive"))
      (node (ref "U20") (pin "7") (pinfunction "QH_7") (pintype "tri_state"))
    )
    (net (code "93") (name "Net-(U20-~{RST})") (class "Default")
      (node (ref "C62") (pin "2") (pinfunction "2_2") (pintype "passive"))
      (node (ref "R167") (pin "1") (pinfunction "1_1") (pintype "passive"))
      (node (ref "U20") (pin "10") (pinfunction "~{RST}_10") (pintype "input"))
    )
    (net (code "94") (name "Net-(U21-QA)") (class "Default")
      (node (ref "R174") (pin "1") (pinfunction "1_1") (pintype "passive"))
      (node (ref "U21") (pin "15") (pinfunction "QA_15") (pintype "tri_state"))
    )
    (net (code "95") (name "Net-(U21-QB)") (class "Default")
      (node (ref "R175") (pin "1") (pinfunction "1_1") (pintype "passive"))
      (node (ref "U21") (pin "1") (pinfunction "QB_1") (pintype "tri_state"))
    )
    (net (code "96") (name "Net-(U21-QC)") (class "Default")
      (node (ref "R176") (pin "1") (pinfunction "1_1") (pintype "passive"))
      (node (ref "U21") (pin "2") (pinfunction "QC_2") (pintype "tri_state"))
    )
    (net (code "97") (name "Net-(U21-QD)") (class "Default")
      (node (ref "R178") (pin "1") (pinfunction "1_1") (pintype "passive"))
      (node (ref "U21") (pin "3") (pinfunction "QD_3") (pintype "tri_state"))
    )
    (net (code "98") (name "Net-(U21-QE)") (class "Default")
      (node (ref "R179") (pin "1") (pinfunction "1_1") (pintype "passive"))
      (node (ref "U21") (pin "4") (pinfunction "QE_4") (pintype "tri_state"))
    )
    (net (code "99") (name "Net-(U21-QF)") (class "Default")
      (node (ref "R180") (pin "1") (pinfunction "1_1") (pintype "passive"))
      (node (ref "U21") (pin "5") (pinfunction "QF_5") (pintype "tri_state"))
    )
    (net (code "100") (name "Net-(U21-QG)") (class "Default")
      (node (ref "R182") (pin "1") (pinfunction "1_1") (pintype "passive"))
      (node (ref "U21") (pin "6") (pinfunction "QG_6") (pintype "tri_state"))
    )
    (net (code "101") (name "Net-(U21-QH)") (class "Default")
      (node (ref "R183") (pin "1") (pinfunction "1_1") (pintype "passive"))
      (node (ref "U21") (pin "7") (pinfunction "QH_7") (pintype "tri_state"))
    )
    (net (code "102") (name "Net-(U21-~{RST})") (class "Default")
      (node (ref "C64") (pin "2") (pinfunction "2_2") (pintype "passive"))
      (node (ref "R177") (pin "1") (pinfunction "1_1") (pintype "passive"))
      (node (ref "U21") (pin "10") (pinfunction "~{RST}_10") (pintype "input"))
    )
    (net (code "103") (name "VSS_SKC") (class "Default")
      (node (ref "C55") (pin "2") (pinfunction "2_2") (pintype "passive"))
      (node (ref "C56") (pin "1") (pinfunction "1_1") (pintype "passive"))
      (node (ref "C57") (pin "2") (pinfunction "2_2") (pintype "passive"))
      (node (ref "C58") (pin "1") (pinfunction "1_1") (pintype "passive"))
      (node (ref "C59") (pin "2") (pinfunction "2_2") (pintype "passive"))
      (node (ref "C60") (pin "1") (pinfunction "1_1") (pintype "passive"))
      (node (ref "C61") (pin "2") (pinfunction "2_2") (pintype "passive"))
      (node (ref "C62") (pin "1") (pinfunction "1_1") (pintype "passive"))
      (node (ref "C63") (pin "2") (pinfunction "2_2") (pintype "passive"))
      (node (ref "C64") (pin "1") (pinfunction "1_1") (pintype "passive"))
      (node (ref "Q1") (pin "2") (pinfunction "E_2") (pintype "passive"))
      (node (ref "Q2") (pin "2") (pinfunction "E_2") (pintype "passive"))
      (node (ref "Q3") (pin "2") (pinfunction "E_2") (pintype "passive"))
      (node (ref "U17") (pin "13") (pinfunction "~{OE}_13") (pintype "input"))
      (node (ref "U17") (pin "8") (pinfunction "GND_8") (pintype "power_in"))
      (node (ref "U18") (pin "13") (pinfunction "~{OE}_13") (pintype "input"))
      (node (ref "U18") (pin "8") (pinfunction "GND_8") (pintype "power_in"))
      (node (ref "U19") (pin "13") (pinfunction "~{OE}_13") (pintype "input"))
      (node (ref "U19") (pin "8") (pinfunction "GND_8") (pintype "power_in"))
      (node (ref "U20") (pin "13") (pinfunction "~{OE}_13") (pintype "input"))
      (node (ref "U20") (pin "8") (pinfunction "GND_8") (pintype "power_in"))
      (node (ref "U21") (pin "13") (pinfunction "~{OE}_13") (pintype "input"))
      (node (ref "U21") (pin "8") (pinfunction "GND_8") (pintype "power_in"))
    )
    (net (code "104") (name "unconnected-(U17-SDO-Pad9)") (class "Default")
      (node (ref "U17") (pin "9") (pinfunction "SDO_9") (pintype "output"))
    )
    (net (code "105") (name "unconnected-(U18-SDO-Pad9)") (class "Default")
      (node (ref "U18") (pin "9") (pinfunction "SDO_9") (pintype "output"))
    )
    (net (code "106") (name "unconnected-(U19-SDO-Pad9)") (class "Default")
      (node (ref "U19") (pin "9") (pinfunction "SDO_9") (pintype "output"))
    )
    (net (code "107") (name "unconnected-(U20-SDO-Pad9)") (class "Default")
      (node (ref "U20") (pin "9") (pinfunction "SDO_9") (pintype "output"))
    )
    (net (code "108") (name "unconnected-(U21-SDO-Pad9)") (class "Default")
      (node (ref "U21") (pin "9") (pinfunction "SDO_9") (pintype "output"))
    )
  )
)
